# VM_Cut_Off.net
KiCad netlist of a schematic drawn in EAGLE
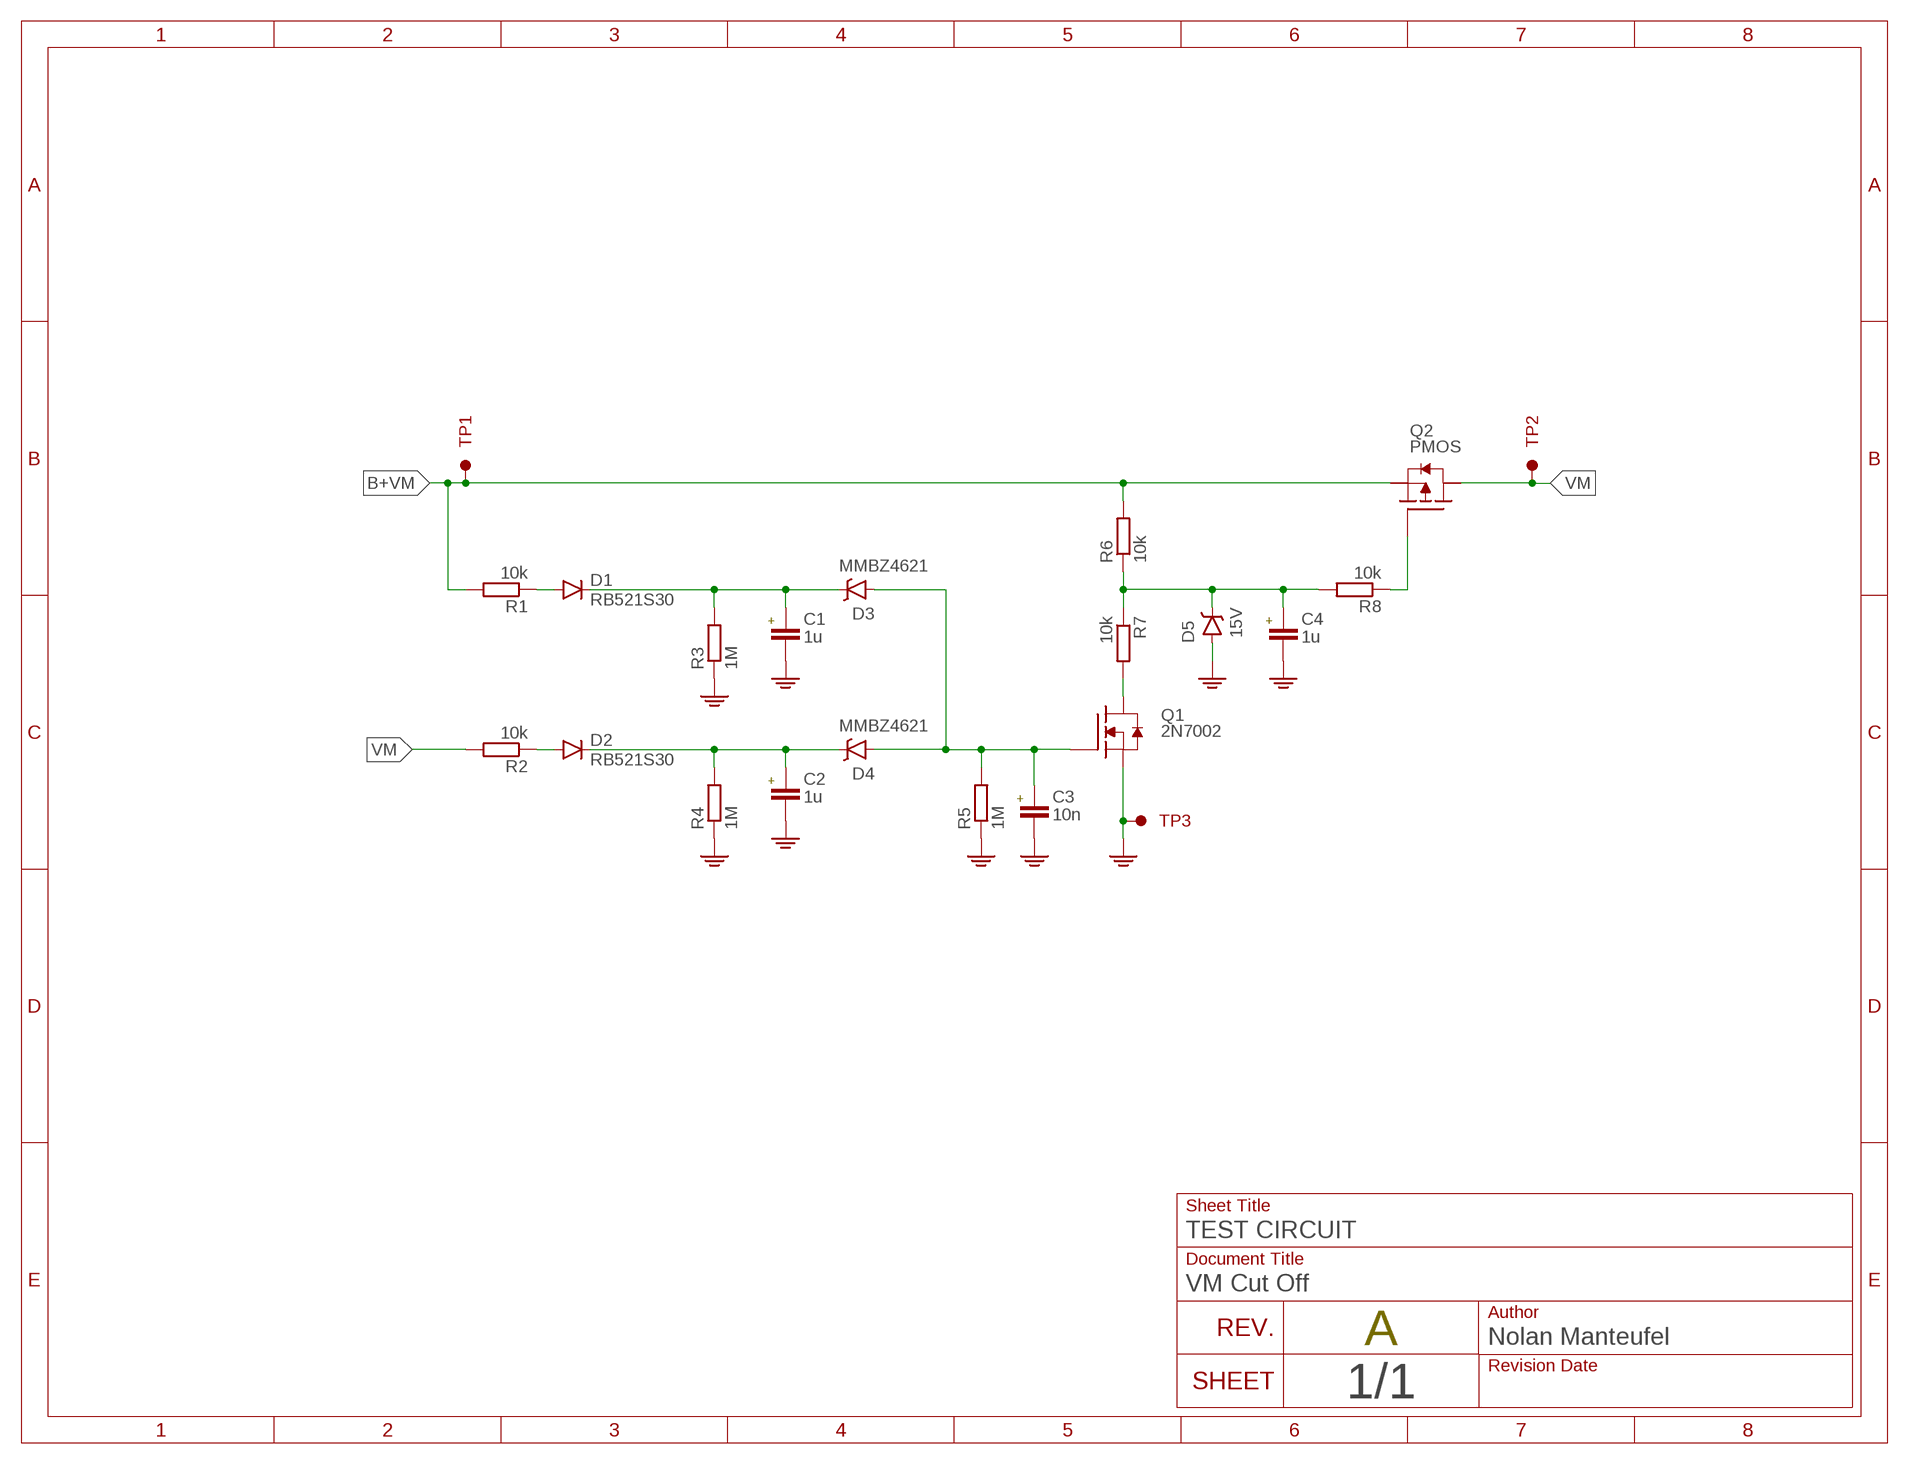
[diagram p0: schematic, sheet 1]

(export (version "E")
  (design (tool "Eeschema 10.0.6"))
  (components
    (comp (ref "C1")
      (value "1u")
      (footprint "eagle-import:C0402")
      (libsource (lib "eagle-import") (part "C-EUC0402"))
    )
    (comp (ref "C2")
      (value "1u")
      (footprint "eagle-import:C0402")
      (libsource (lib "eagle-import") (part "C-EUC0402"))
    )
    (comp (ref "C3")
      (value "10n")
      (footprint "eagle-import:C0402")
      (libsource (lib "eagle-import") (part "C-EUC0402"))
    )
    (comp (ref "C4")
      (value "1u")
      (footprint "eagle-import:C0402")
      (libsource (lib "eagle-import") (part "C-EUC0402"))
    )
    (comp (ref "D1")
      (value "RB521S30")
      (footprint "eagle-import:SC79_INFINEON")
      (libsource (lib "eagle-import") (part "DIODE-SC79_INFINEON"))
    )
    (comp (ref "D2")
      (value "RB521S30")
      (footprint "eagle-import:SC79_INFINEON")
      (libsource (lib "eagle-import") (part "DIODE-SC79_INFINEON"))
    )
    (comp (ref "D3")
      (value "MMBZ4621")
      (footprint "eagle-import:SOT23")
      (libsource (lib "eagle-import") (part "ZENER-DIODESOT23"))
    )
    (comp (ref "D4")
      (value "MMBZ4621")
      (footprint "eagle-import:SOT23")
      (libsource (lib "eagle-import") (part "ZENER-DIODESOT23"))
    )
    (comp (ref "D5")
      (value "15V")
      (footprint "eagle-import:SOT23")
      (libsource (lib "eagle-import") (part "ZENER-DIODESOT23"))
    )
    (comp (ref "Q1")
      (value "2N7002")
      (footprint "eagle-import:SOT23")
      (libsource (lib "eagle-import") (part "MOSFET-NSOT23"))
    )
    (comp (ref "Q2")
      (value "PMOS")
      (footprint "eagle-import:SOT23")
      (libsource (lib "eagle-import") (part "MOSFET-PNTR2101PT1G"))
    )
    (comp (ref "R1")
      (value "10k")
      (footprint "eagle-import:R0402")
      (libsource (lib "eagle-import") (part "R-EU_R0402"))
    )
    (comp (ref "R2")
      (value "10k")
      (footprint "eagle-import:R0402")
      (libsource (lib "eagle-import") (part "R-EU_R0402"))
    )
    (comp (ref "R3")
      (value "1M")
      (footprint "eagle-import:R0402")
      (libsource (lib "eagle-import") (part "R-EU_R0402"))
    )
    (comp (ref "R4")
      (value "1M")
      (footprint "eagle-import:R0402")
      (libsource (lib "eagle-import") (part "R-EU_R0402"))
    )
    (comp (ref "R5")
      (value "1M")
      (footprint "eagle-import:R0402")
      (libsource (lib "eagle-import") (part "R-EU_R0402"))
    )
    (comp (ref "R6")
      (value "10k")
      (footprint "eagle-import:R0402")
      (libsource (lib "eagle-import") (part "R-EU_R0402"))
    )
    (comp (ref "R7")
      (value "10k")
      (footprint "eagle-import:R0402")
      (libsource (lib "eagle-import") (part "R-EU_R0402"))
    )
    (comp (ref "R8")
      (value "10k")
      (footprint "eagle-import:R0402")
      (libsource (lib "eagle-import") (part "R-EU_R0402"))
    )
    (comp (ref "TP1")
      (value "PWR")
      (footprint "eagle-import:PINS_1_TESTPOINT_KE5000_NOTEXT")
      (libsource (lib "eagle-import") (part "TESTPOINTKE5000-SMTEXT"))
    )
    (comp (ref "TP2")
      (value "OUT")
      (footprint "eagle-import:PINS_1_TESTPOINT_KE5000_NOTEXT")
      (libsource (lib "eagle-import") (part "TESTPOINTKE5000-SMTEXT"))
    )
    (comp (ref "TP3")
      (value "GND")
      (footprint "eagle-import:PINS_1_TESTPOINT_KE5000_NOTEXT")
      (libsource (lib "eagle-import") (part "TESTPOINTKE5000-SMTEXT"))
    )
  )
  (nets
    (net (code "1") (name "B+VM") (class "Default")
      (node (ref "Q2") (pin "3") (pinfunction "S_3") (pintype "passive"))
      (node (ref "R1") (pin "2") (pinfunction "2_2") (pintype "passive"))
      (node (ref "R6") (pin "2") (pinfunction "2_2") (pintype "passive"))
      (node (ref "TP1") (pin "1") (pinfunction "1_1") (pintype "bidirectional"))
    )
    (net (code "2") (name "GND") (class "Default")
      (node (ref "C1") (pin "2") (pinfunction "2_2") (pintype "passive"))
      (node (ref "C2") (pin "2") (pinfunction "2_2") (pintype "passive"))
      (node (ref "C3") (pin "2") (pinfunction "2_2") (pintype "passive"))
      (node (ref "C4") (pin "2") (pinfunction "2_2") (pintype "passive"))
      (node (ref "D5") (pin "1") (pinfunction "A_1") (pintype "passive"))
      (node (ref "Q1") (pin "2") (pinfunction "S_2") (pintype "passive"))
      (node (ref "R3") (pin "1") (pinfunction "1_1") (pintype "passive"))
      (node (ref "R4") (pin "1") (pinfunction "1_1") (pintype "passive"))
      (node (ref "R5") (pin "1") (pinfunction "1_1") (pintype "passive"))
      (node (ref "TP3") (pin "1") (pinfunction "1_1") (pintype "bidirectional"))
    )
    (net (code "3") (name "Net-(D1-PadA)") (class "Default")
      (node (ref "D1") (pin "A") (pinfunction "A_A") (pintype "passive"))
      (node (ref "R1") (pin "1") (pinfunction "1_1") (pintype "passive"))
    )
    (net (code "4") (name "Net-(D2-PadA)") (class "Default")
      (node (ref "D2") (pin "A") (pinfunction "A_A") (pintype "passive"))
      (node (ref "R2") (pin "1") (pinfunction "1_1") (pintype "passive"))
    )
    (net (code "5") (name "Net-(D3-A)") (class "Default")
      (node (ref "C3") (pin "1") (pinfunction "1_1") (pintype "passive"))
      (node (ref "D3") (pin "1") (pinfunction "A_1") (pintype "passive"))
      (node (ref "D4") (pin "1") (pinfunction "A_1") (pintype "passive"))
      (node (ref "Q1") (pin "1") (pinfunction "G_1") (pintype "passive"))
      (node (ref "R5") (pin "2") (pinfunction "2_2") (pintype "passive"))
    )
    (net (code "6") (name "Net-(D3-C)") (class "Default")
      (node (ref "C1") (pin "1") (pinfunction "1_1") (pintype "passive"))
      (node (ref "D1") (pin "C") (pinfunction "C_C") (pintype "passive"))
      (node (ref "D3") (pin "3") (pinfunction "C_3") (pintype "passive"))
      (node (ref "R3") (pin "2") (pinfunction "2_2") (pintype "passive"))
    )
    (net (code "7") (name "Net-(D4-C)") (class "Default")
      (node (ref "C2") (pin "1") (pinfunction "1_1") (pintype "passive"))
      (node (ref "D2") (pin "C") (pinfunction "C_C") (pintype "passive"))
      (node (ref "D4") (pin "3") (pinfunction "C_3") (pintype "passive"))
      (node (ref "R4") (pin "2") (pinfunction "2_2") (pintype "passive"))
    )
    (net (code "8") (name "Net-(D5-C)") (class "Default")
      (node (ref "C4") (pin "1") (pinfunction "1_1") (pintype "passive"))
      (node (ref "D5") (pin "3") (pinfunction "C_3") (pintype "passive"))
      (node (ref "R6") (pin "1") (pinfunction "1_1") (pintype "passive"))
      (node (ref "R7") (pin "1") (pinfunction "1_1") (pintype "passive"))
      (node (ref "R8") (pin "2") (pinfunction "2_2") (pintype "passive"))
    )
    (net (code "9") (name "Net-(Q1-D)") (class "Default")
      (node (ref "Q1") (pin "3") (pinfunction "D_3") (pintype "passive"))
      (node (ref "R7") (pin "2") (pinfunction "2_2") (pintype "passive"))
    )
    (net (code "10") (name "Net-(Q2-G)") (class "Default")
      (node (ref "Q2") (pin "1") (pinfunction "G_1") (pintype "passive"))
      (node (ref "R8") (pin "1") (pinfunction "1_1") (pintype "passive"))
    )
    (net (code "11") (name "VM") (class "Default")
      (node (ref "Q2") (pin "2") (pinfunction "D_2") (pintype "passive"))
      (node (ref "R2") (pin "2") (pinfunction "2_2") (pintype "passive"))
      (node (ref "TP2") (pin "1") (pinfunction "1_1") (pintype "bidirectional"))
    )
  )
)
